# S602X.net
KiCad netlist of a schematic drawn in EAGLE
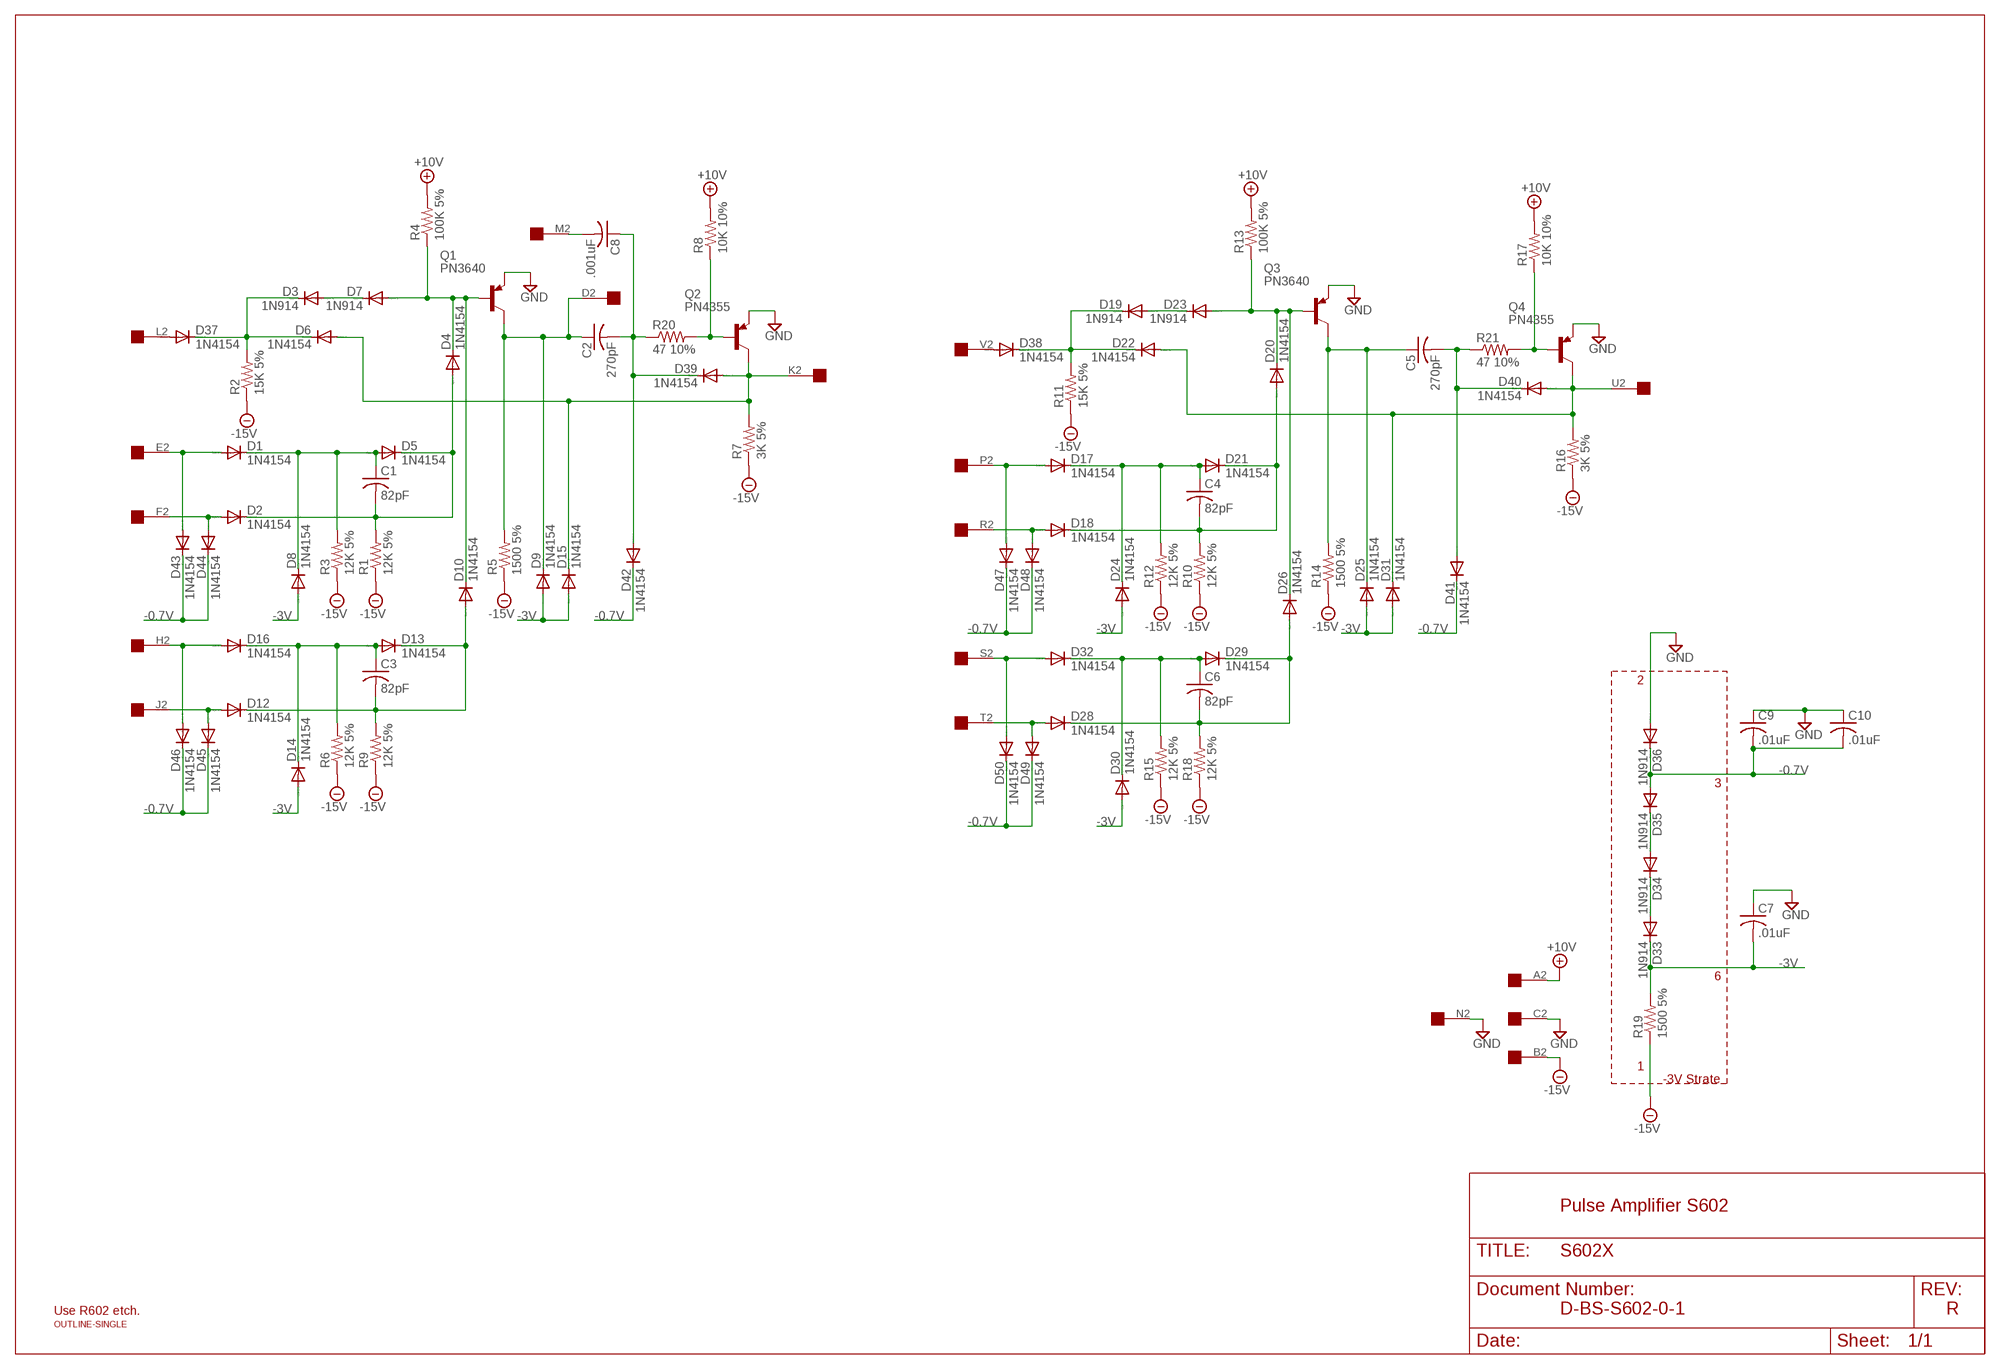
[diagram p0: schematic, sheet 1]

(export (version "E")
  (design (tool "Eeschema 10.0.6"))
  (components
    (comp (ref "C1")
      (value "82pF")
      (footprint "eagle-import:C050-025X075")
      (libsource (lib "eagle-import") (part "C-US050-025X075"))
    )
    (comp (ref "C2")
      (value "270pF")
      (footprint "eagle-import:C050-025X075")
      (libsource (lib "eagle-import") (part "C-US050-025X075"))
    )
    (comp (ref "C3")
      (value "82pF")
      (footprint "eagle-import:C050-025X075")
      (libsource (lib "eagle-import") (part "C-US050-025X075"))
    )
    (comp (ref "C4")
      (value "82pF")
      (footprint "eagle-import:C050-025X075")
      (libsource (lib "eagle-import") (part "C-US050-025X075"))
    )
    (comp (ref "C5")
      (value "270pF")
      (footprint "eagle-import:C050-025X075")
      (libsource (lib "eagle-import") (part "C-US050-025X075"))
    )
    (comp (ref "C6")
      (value "82pF")
      (footprint "eagle-import:C050-025X075")
      (libsource (lib "eagle-import") (part "C-US050-025X075"))
    )
    (comp (ref "C7")
      (value ".01uF")
      (footprint "eagle-import:C075-032X103")
      (libsource (lib "eagle-import") (part "C-US075-032X103"))
    )
    (comp (ref "C8")
      (value ".001uF")
      (footprint "eagle-import:C050-025X075")
      (libsource (lib "eagle-import") (part "C-US050-025X075"))
    )
    (comp (ref "C9")
      (value ".01uF")
      (footprint "eagle-import:C050-025X075")
      (libsource (lib "eagle-import") (part "C-US050-025X075"))
    )
    (comp (ref "C10")
      (value ".01uF")
      (footprint "eagle-import:C050-025X075")
      (libsource (lib "eagle-import") (part "C-US050-025X075"))
    )
    (comp (ref "D1")
      (value "1N4154")
      (footprint "eagle-import:DO35-10")
      (libsource (lib "eagle-import") (part "1N4148DO35-10"))
    )
    (comp (ref "D2")
      (value "1N4154")
      (footprint "eagle-import:DO35-10")
      (libsource (lib "eagle-import") (part "1N4148DO35-10"))
    )
    (comp (ref "D3")
      (value "1N914")
      (footprint "eagle-import:DO35-10")
      (libsource (lib "eagle-import") (part "1N4148DO35-10"))
    )
    (comp (ref "D4")
      (value "1N4154")
      (footprint "eagle-import:DO35-10")
      (libsource (lib "eagle-import") (part "1N4148DO35-10"))
    )
    (comp (ref "D5")
      (value "1N4154")
      (footprint "eagle-import:DO35-10")
      (libsource (lib "eagle-import") (part "1N4148DO35-10"))
    )
    (comp (ref "D6")
      (value "1N4154")
      (footprint "eagle-import:DO35-10")
      (libsource (lib "eagle-import") (part "1N4148DO35-10"))
    )
    (comp (ref "D7")
      (value "1N914")
      (footprint "eagle-import:DO35-10")
      (libsource (lib "eagle-import") (part "1N4148DO35-10"))
    )
    (comp (ref "D8")
      (value "1N4154")
      (footprint "eagle-import:DO35-10")
      (libsource (lib "eagle-import") (part "1N4148DO35-10"))
    )
    (comp (ref "D9")
      (value "1N4154")
      (footprint "eagle-import:DO35-10")
      (libsource (lib "eagle-import") (part "1N4148DO35-10"))
    )
    (comp (ref "D10")
      (value "1N4154")
      (footprint "eagle-import:DO35-10")
      (libsource (lib "eagle-import") (part "1N4148DO35-10"))
    )
    (comp (ref "D12")
      (value "1N4154")
      (footprint "eagle-import:DO35-10")
      (libsource (lib "eagle-import") (part "1N4148DO35-10"))
    )
    (comp (ref "D13")
      (value "1N4154")
      (footprint "eagle-import:DO35-10")
      (libsource (lib "eagle-import") (part "1N4148DO35-10"))
    )
    (comp (ref "D14")
      (value "1N4154")
      (footprint "eagle-import:DO35-10")
      (libsource (lib "eagle-import") (part "1N4148DO35-10"))
    )
    (comp (ref "D15")
      (value "1N4154")
      (footprint "eagle-import:DO35-10")
      (libsource (lib "eagle-import") (part "1N4148DO35-10"))
    )
    (comp (ref "D16")
      (value "1N4154")
      (footprint "eagle-import:DO35-10")
      (libsource (lib "eagle-import") (part "1N4148DO35-10"))
    )
    (comp (ref "D17")
      (value "1N4154")
      (footprint "eagle-import:DO35-10")
      (libsource (lib "eagle-import") (part "1N4148DO35-10"))
    )
    (comp (ref "D18")
      (value "1N4154")
      (footprint "eagle-import:DO35-10")
      (libsource (lib "eagle-import") (part "1N4148DO35-10"))
    )
    (comp (ref "D19")
      (value "1N914")
      (footprint "eagle-import:DO35-10")
      (libsource (lib "eagle-import") (part "1N4148DO35-10"))
    )
    (comp (ref "D20")
      (value "1N4154")
      (footprint "eagle-import:DO35-10")
      (libsource (lib "eagle-import") (part "1N4148DO35-10"))
    )
    (comp (ref "D21")
      (value "1N4154")
      (footprint "eagle-import:DO35-10")
      (libsource (lib "eagle-import") (part "1N4148DO35-10"))
    )
    (comp (ref "D22")
      (value "1N4154")
      (footprint "eagle-import:DO35-10")
      (libsource (lib "eagle-import") (part "1N4148DO35-10"))
    )
    (comp (ref "D23")
      (value "1N914")
      (footprint "eagle-import:DO35-10")
      (libsource (lib "eagle-import") (part "1N4148DO35-10"))
    )
    (comp (ref "D24")
      (value "1N4154")
      (footprint "eagle-import:DO35-10")
      (libsource (lib "eagle-import") (part "1N4148DO35-10"))
    )
    (comp (ref "D25")
      (value "1N4154")
      (footprint "eagle-import:DO35-10")
      (libsource (lib "eagle-import") (part "1N4148DO35-10"))
    )
    (comp (ref "D26")
      (value "1N4154")
      (footprint "eagle-import:DO35-10")
      (libsource (lib "eagle-import") (part "1N4148DO35-10"))
    )
    (comp (ref "D28")
      (value "1N4154")
      (footprint "eagle-import:DO35-10")
      (libsource (lib "eagle-import") (part "1N4148DO35-10"))
    )
    (comp (ref "D29")
      (value "1N4154")
      (footprint "eagle-import:DO35-10")
      (libsource (lib "eagle-import") (part "1N4148DO35-10"))
    )
    (comp (ref "D30")
      (value "1N4154")
      (footprint "eagle-import:DO35-10")
      (libsource (lib "eagle-import") (part "1N4148DO35-10"))
    )
    (comp (ref "D31")
      (value "1N4154")
      (footprint "eagle-import:DO35-10")
      (libsource (lib "eagle-import") (part "1N4148DO35-10"))
    )
    (comp (ref "D32")
      (value "1N4154")
      (footprint "eagle-import:DO35-10")
      (libsource (lib "eagle-import") (part "1N4148DO35-10"))
    )
    (comp (ref "D33")
      (value "1N914")
      (footprint "eagle-import:DO35-10")
      (libsource (lib "eagle-import") (part "1N4148DO35-10"))
    )
    (comp (ref "D34")
      (value "1N914")
      (footprint "eagle-import:DO35-10")
      (libsource (lib "eagle-import") (part "1N4148DO35-10"))
    )
    (comp (ref "D35")
      (value "1N914")
      (footprint "eagle-import:DO35-10")
      (libsource (lib "eagle-import") (part "1N4148DO35-10"))
    )
    (comp (ref "D36")
      (value "1N914")
      (footprint "eagle-import:DO35-10")
      (libsource (lib "eagle-import") (part "1N4148DO35-10"))
    )
    (comp (ref "D37")
      (value "1N4154")
      (footprint "eagle-import:DO35-10")
      (libsource (lib "eagle-import") (part "1N4148DO35-10"))
    )
    (comp (ref "D38")
      (value "1N4154")
      (footprint "eagle-import:DO35-10")
      (libsource (lib "eagle-import") (part "1N4148DO35-10"))
    )
    (comp (ref "D39")
      (value "1N4154")
      (footprint "eagle-import:DO35-10")
      (libsource (lib "eagle-import") (part "1N4148DO35-10"))
    )
    (comp (ref "D40")
      (value "1N4154")
      (footprint "eagle-import:DO35-10")
      (libsource (lib "eagle-import") (part "1N4148DO35-10"))
    )
    (comp (ref "D41")
      (value "1N4154")
      (footprint "eagle-import:DO35-10")
      (libsource (lib "eagle-import") (part "1N4148DO35-10"))
    )
    (comp (ref "D42")
      (value "1N4154")
      (footprint "eagle-import:DO35-10")
      (libsource (lib "eagle-import") (part "1N4148DO35-10"))
    )
    (comp (ref "D43")
      (value "1N4154")
      (footprint "eagle-import:DO35-10")
      (libsource (lib "eagle-import") (part "1N4148DO35-10"))
    )
    (comp (ref "D44")
      (value "1N4154")
      (footprint "eagle-import:DO35-10")
      (libsource (lib "eagle-import") (part "1N4148DO35-10"))
    )
    (comp (ref "D45")
      (value "1N4154")
      (footprint "eagle-import:DO35-10")
      (libsource (lib "eagle-import") (part "1N4148DO35-10"))
    )
    (comp (ref "D46")
      (value "1N4154")
      (footprint "eagle-import:DO35-10")
      (libsource (lib "eagle-import") (part "1N4148DO35-10"))
    )
    (comp (ref "D47")
      (value "1N4154")
      (footprint "eagle-import:DO35-10")
      (libsource (lib "eagle-import") (part "1N4148DO35-10"))
    )
    (comp (ref "D48")
      (value "1N4154")
      (footprint "eagle-import:DO35-10")
      (libsource (lib "eagle-import") (part "1N4148DO35-10"))
    )
    (comp (ref "D49")
      (value "1N4154")
      (footprint "eagle-import:DO35-10")
      (libsource (lib "eagle-import") (part "1N4148DO35-10"))
    )
    (comp (ref "D50")
      (value "1N4154")
      (footprint "eagle-import:DO35-10")
      (libsource (lib "eagle-import") (part "1N4148DO35-10"))
    )
    (comp (ref "Q1")
      (value "PN3640")
      (footprint "eagle-import:TO39")
      (libsource (lib "eagle-import") (part "2N2904"))
    )
    (comp (ref "Q2")
      (value "PN4355")
      (footprint "eagle-import:TO39")
      (libsource (lib "eagle-import") (part "2N2904"))
    )
    (comp (ref "Q3")
      (value "PN3640")
      (footprint "eagle-import:TO39")
      (libsource (lib "eagle-import") (part "2N2904"))
    )
    (comp (ref "Q4")
      (value "PN4355")
      (footprint "eagle-import:TO39")
      (libsource (lib "eagle-import") (part "2N2904"))
    )
    (comp (ref "R1")
      (value "12K 5%")
      (footprint "eagle-import:0207_10")
      (libsource (lib "eagle-import") (part "R-US_0207/10"))
    )
    (comp (ref "R2")
      (value "15K 5%")
      (footprint "eagle-import:0207_10")
      (libsource (lib "eagle-import") (part "R-US_0207/10"))
    )
    (comp (ref "R3")
      (value "12K 5%")
      (footprint "eagle-import:0207_10")
      (libsource (lib "eagle-import") (part "R-US_0207/10"))
    )
    (comp (ref "R4")
      (value "100K 5%")
      (footprint "eagle-import:0207_10")
      (libsource (lib "eagle-import") (part "R-US_0207/10"))
    )
    (comp (ref "R5")
      (value "1500 5%")
      (footprint "eagle-import:0207_10")
      (libsource (lib "eagle-import") (part "R-US_0207/10"))
    )
    (comp (ref "R6")
      (value "12K 5%")
      (footprint "eagle-import:0207_10")
      (libsource (lib "eagle-import") (part "R-US_0207/10"))
    )
    (comp (ref "R7")
      (value "3K 5%")
      (footprint "eagle-import:0207_10")
      (libsource (lib "eagle-import") (part "R-US_0207/10"))
    )
    (comp (ref "R8")
      (value "10K 10%")
      (footprint "eagle-import:0207_10")
      (libsource (lib "eagle-import") (part "R-US_0207/10"))
    )
    (comp (ref "R9")
      (value "12K 5%")
      (footprint "eagle-import:0207_10")
      (libsource (lib "eagle-import") (part "R-US_0207/10"))
    )
    (comp (ref "R10")
      (value "12K 5%")
      (footprint "eagle-import:0207_10")
      (libsource (lib "eagle-import") (part "R-US_0207/10"))
    )
    (comp (ref "R11")
      (value "15K 5%")
      (footprint "eagle-import:0207_10")
      (libsource (lib "eagle-import") (part "R-US_0207/10"))
    )
    (comp (ref "R12")
      (value "12K 5%")
      (footprint "eagle-import:0207_10")
      (libsource (lib "eagle-import") (part "R-US_0207/10"))
    )
    (comp (ref "R13")
      (value "100K 5%")
      (footprint "eagle-import:0207_10")
      (libsource (lib "eagle-import") (part "R-US_0207/10"))
    )
    (comp (ref "R14")
      (value "1500 5%")
      (footprint "eagle-import:0207_10")
      (libsource (lib "eagle-import") (part "R-US_0207/10"))
    )
    (comp (ref "R15")
      (value "12K 5%")
      (footprint "eagle-import:0207_10")
      (libsource (lib "eagle-import") (part "R-US_0207/10"))
    )
    (comp (ref "R16")
      (value "3K 5%")
      (footprint "eagle-import:0207_10")
      (libsource (lib "eagle-import") (part "R-US_0207/10"))
    )
    (comp (ref "R17")
      (value "10K 10%")
      (footprint "eagle-import:0207_10")
      (libsource (lib "eagle-import") (part "R-US_0207/10"))
    )
    (comp (ref "R18")
      (value "12K 5%")
      (footprint "eagle-import:0207_10")
      (libsource (lib "eagle-import") (part "R-US_0207/10"))
    )
    (comp (ref "R19")
      (value "1500 5%")
      (footprint "eagle-import:0207_10")
      (libsource (lib "eagle-import") (part "R-US_0207/10"))
    )
    (comp (ref "R20")
      (value "47 10%")
      (footprint "eagle-import:0207_10")
      (libsource (lib "eagle-import") (part "R-US_0207/10"))
    )
    (comp (ref "R21")
      (value "47 10%")
      (footprint "eagle-import:0207_10")
      (libsource (lib "eagle-import") (part "R-US_0207/10"))
    )
    (comp (ref "U$1")
      (value "OUTLINE-SINGLE")
      (footprint "eagle-import:SINGLE")
      (libsource (lib "eagle-import") (part "OUTLINE-SINGLE"))
    )
    (comp (ref "U$2")
      (value "EDGE-1")
      (footprint "eagle-import:EDGE-CON1")
      (libsource (lib "eagle-import") (part "EDGE-1"))
    )
  )
  (nets
    (net (code "1") (name "+10V") (class "Default")
      (node (ref "R13") (pin "2") (pinfunction "2_2") (pintype "passive"))
      (node (ref "R17") (pin "2") (pinfunction "2_2") (pintype "passive"))
      (node (ref "R4") (pin "2") (pinfunction "2_2") (pintype "passive"))
      (node (ref "R8") (pin "2") (pinfunction "2_2") (pintype "passive"))
      (node (ref "U$2") (pin "A2") (pinfunction "1_A2") (pintype "bidirectional"))
    )
    (net (code "2") (name "-15V") (class "Default")
      (node (ref "R1") (pin "1") (pinfunction "1_1") (pintype "passive"))
      (node (ref "R10") (pin "1") (pinfunction "1_1") (pintype "passive"))
      (node (ref "R11") (pin "1") (pinfunction "1_1") (pintype "passive"))
      (node (ref "R12") (pin "1") (pinfunction "1_1") (pintype "passive"))
      (node (ref "R14") (pin "1") (pinfunction "1_1") (pintype "passive"))
      (node (ref "R15") (pin "1") (pinfunction "1_1") (pintype "passive"))
      (node (ref "R16") (pin "1") (pinfunction "1_1") (pintype "passive"))
      (node (ref "R18") (pin "1") (pinfunction "1_1") (pintype "passive"))
      (node (ref "R19") (pin "1") (pinfunction "1_1") (pintype "passive"))
      (node (ref "R2") (pin "1") (pinfunction "1_1") (pintype "passive"))
      (node (ref "R3") (pin "1") (pinfunction "1_1") (pintype "passive"))
      (node (ref "R5") (pin "1") (pinfunction "1_1") (pintype "passive"))
      (node (ref "R6") (pin "1") (pinfunction "1_1") (pintype "passive"))
      (node (ref "R7") (pin "1") (pinfunction "1_1") (pintype "passive"))
      (node (ref "R9") (pin "1") (pinfunction "1_1") (pintype "passive"))
      (node (ref "U$2") (pin "B2") (pinfunction "1_B2") (pintype "bidirectional"))
    )
    (net (code "3") (name "/-0.7V") (class "Default")
      (node (ref "C10") (pin "2") (pinfunction "2_2") (pintype "passive"))
      (node (ref "C9") (pin "2") (pinfunction "2_2") (pintype "passive"))
      (node (ref "D35") (pin "A") (pinfunction "A_A") (pintype "passive"))
      (node (ref "D36") (pin "C") (pinfunction "C_C") (pintype "passive"))
      (node (ref "D41") (pin "C") (pinfunction "C_C") (pintype "passive"))
      (node (ref "D42") (pin "C") (pinfunction "C_C") (pintype "passive"))
      (node (ref "D43") (pin "C") (pinfunction "C_C") (pintype "passive"))
      (node (ref "D44") (pin "C") (pinfunction "C_C") (pintype "passive"))
      (node (ref "D45") (pin "C") (pinfunction "C_C") (pintype "passive"))
      (node (ref "D46") (pin "C") (pinfunction "C_C") (pintype "passive"))
      (node (ref "D47") (pin "C") (pinfunction "C_C") (pintype "passive"))
      (node (ref "D48") (pin "C") (pinfunction "C_C") (pintype "passive"))
      (node (ref "D49") (pin "C") (pinfunction "C_C") (pintype "passive"))
      (node (ref "D50") (pin "C") (pinfunction "C_C") (pintype "passive"))
    )
    (net (code "4") (name "/-3V") (class "Default")
      (node (ref "C7") (pin "2") (pinfunction "2_2") (pintype "passive"))
      (node (ref "D14") (pin "A") (pinfunction "A_A") (pintype "passive"))
      (node (ref "D15") (pin "A") (pinfunction "A_A") (pintype "passive"))
      (node (ref "D24") (pin "A") (pinfunction "A_A") (pintype "passive"))
      (node (ref "D25") (pin "A") (pinfunction "A_A") (pintype "passive"))
      (node (ref "D30") (pin "A") (pinfunction "A_A") (pintype "passive"))
      (node (ref "D31") (pin "A") (pinfunction "A_A") (pintype "passive"))
      (node (ref "D33") (pin "C") (pinfunction "C_C") (pintype "passive"))
      (node (ref "D8") (pin "A") (pinfunction "A_A") (pintype "passive"))
      (node (ref "D9") (pin "A") (pinfunction "A_A") (pintype "passive"))
      (node (ref "R19") (pin "2") (pinfunction "2_2") (pintype "passive"))
    )
    (net (code "5") (name "GND") (class "Default")
      (node (ref "C10") (pin "1") (pinfunction "1_1") (pintype "passive"))
      (node (ref "C7") (pin "1") (pinfunction "1_1") (pintype "passive"))
      (node (ref "C9") (pin "1") (pinfunction "1_1") (pintype "passive"))
      (node (ref "D36") (pin "A") (pinfunction "A_A") (pintype "passive"))
      (node (ref "Q1") (pin "1") (pinfunction "E_1") (pintype "passive"))
      (node (ref "Q2") (pin "1") (pinfunction "E_1") (pintype "passive"))
      (node (ref "Q3") (pin "1") (pinfunction "E_1") (pintype "passive"))
      (node (ref "Q4") (pin "1") (pinfunction "E_1") (pintype "passive"))
      (node (ref "U$2") (pin "C2") (pinfunction "1_C2") (pintype "bidirectional"))
      (node (ref "U$2") (pin "N2") (pinfunction "1_N2") (pintype "bidirectional"))
    )
    (net (code "6") (name "Net-(C1-Pad1)") (class "Default")
      (node (ref "C1") (pin "1") (pinfunction "1_1") (pintype "passive"))
      (node (ref "D1") (pin "C") (pinfunction "C_C") (pintype "passive"))
      (node (ref "D5") (pin "A") (pinfunction "A_A") (pintype "passive"))
      (node (ref "D8") (pin "C") (pinfunction "C_C") (pintype "passive"))
      (node (ref "R3") (pin "2") (pinfunction "2_2") (pintype "passive"))
    )
    (net (code "7") (name "Net-(C1-Pad2)") (class "Default")
      (node (ref "C1") (pin "2") (pinfunction "2_2") (pintype "passive"))
      (node (ref "D2") (pin "C") (pinfunction "C_C") (pintype "passive"))
      (node (ref "D4") (pin "A") (pinfunction "A_A") (pintype "passive"))
      (node (ref "D5") (pin "C") (pinfunction "C_C") (pintype "passive"))
      (node (ref "R1") (pin "2") (pinfunction "2_2") (pintype "passive"))
    )
    (net (code "8") (name "Net-(C2-Pad2)") (class "Default")
      (node (ref "C2") (pin "2") (pinfunction "2_2") (pintype "passive"))
      (node (ref "C8") (pin "1") (pinfunction "1_1") (pintype "passive"))
      (node (ref "D39") (pin "C") (pinfunction "C_C") (pintype "passive"))
      (node (ref "D42") (pin "A") (pinfunction "A_A") (pintype "passive"))
      (node (ref "R20") (pin "1") (pinfunction "1_1") (pintype "passive"))
    )
    (net (code "9") (name "Net-(C3-Pad1)") (class "Default")
      (node (ref "C3") (pin "1") (pinfunction "1_1") (pintype "passive"))
      (node (ref "D13") (pin "A") (pinfunction "A_A") (pintype "passive"))
      (node (ref "D14") (pin "C") (pinfunction "C_C") (pintype "passive"))
      (node (ref "D16") (pin "C") (pinfunction "C_C") (pintype "passive"))
      (node (ref "R6") (pin "2") (pinfunction "2_2") (pintype "passive"))
    )
    (net (code "10") (name "Net-(C3-Pad2)") (class "Default")
      (node (ref "C3") (pin "2") (pinfunction "2_2") (pintype "passive"))
      (node (ref "D10") (pin "A") (pinfunction "A_A") (pintype "passive"))
      (node (ref "D12") (pin "C") (pinfunction "C_C") (pintype "passive"))
      (node (ref "D13") (pin "C") (pinfunction "C_C") (pintype "passive"))
      (node (ref "R9") (pin "2") (pinfunction "2_2") (pintype "passive"))
    )
    (net (code "11") (name "Net-(C4-Pad1)") (class "Default")
      (node (ref "C4") (pin "1") (pinfunction "1_1") (pintype "passive"))
      (node (ref "D17") (pin "C") (pinfunction "C_C") (pintype "passive"))
      (node (ref "D21") (pin "A") (pinfunction "A_A") (pintype "passive"))
      (node (ref "D24") (pin "C") (pinfunction "C_C") (pintype "passive"))
      (node (ref "R12") (pin "2") (pinfunction "2_2") (pintype "passive"))
    )
    (net (code "12") (name "Net-(C4-Pad2)") (class "Default")
      (node (ref "C4") (pin "2") (pinfunction "2_2") (pintype "passive"))
      (node (ref "D18") (pin "C") (pinfunction "C_C") (pintype "passive"))
      (node (ref "D20") (pin "A") (pinfunction "A_A") (pintype "passive"))
      (node (ref "D21") (pin "C") (pinfunction "C_C") (pintype "passive"))
      (node (ref "R10") (pin "2") (pinfunction "2_2") (pintype "passive"))
    )
    (net (code "13") (name "Net-(C5-Pad2)") (class "Default")
      (node (ref "C5") (pin "2") (pinfunction "2_2") (pintype "passive"))
      (node (ref "D40") (pin "C") (pinfunction "C_C") (pintype "passive"))
      (node (ref "D41") (pin "A") (pinfunction "A_A") (pintype "passive"))
      (node (ref "R21") (pin "1") (pinfunction "1_1") (pintype "passive"))
    )
    (net (code "14") (name "Net-(C6-Pad1)") (class "Default")
      (node (ref "C6") (pin "1") (pinfunction "1_1") (pintype "passive"))
      (node (ref "D29") (pin "A") (pinfunction "A_A") (pintype "passive"))
      (node (ref "D30") (pin "C") (pinfunction "C_C") (pintype "passive"))
      (node (ref "D32") (pin "C") (pinfunction "C_C") (pintype "passive"))
      (node (ref "R15") (pin "2") (pinfunction "2_2") (pintype "passive"))
    )
    (net (code "15") (name "Net-(C6-Pad2)") (class "Default")
      (node (ref "C6") (pin "2") (pinfunction "2_2") (pintype "passive"))
      (node (ref "D26") (pin "A") (pinfunction "A_A") (pintype "passive"))
      (node (ref "D28") (pin "C") (pinfunction "C_C") (pintype "passive"))
      (node (ref "D29") (pin "C") (pinfunction "C_C") (pintype "passive"))
      (node (ref "R18") (pin "2") (pinfunction "2_2") (pintype "passive"))
    )
    (net (code "16") (name "Net-(D3-PadA)") (class "Default")
      (node (ref "D3") (pin "A") (pinfunction "A_A") (pintype "passive"))
      (node (ref "D7") (pin "C") (pinfunction "C_C") (pintype "passive"))
    )
    (net (code "17") (name "Net-(D3-PadC)") (class "Default")
      (node (ref "D3") (pin "C") (pinfunction "C_C") (pintype "passive"))
      (node (ref "D37") (pin "C") (pinfunction "C_C") (pintype "passive"))
      (node (ref "D6") (pin "C") (pinfunction "C_C") (pintype "passive"))
      (node (ref "R2") (pin "2") (pinfunction "2_2") (pintype "passive"))
    )
    (net (code "18") (name "Net-(D19-PadA)") (class "Default")
      (node (ref "D19") (pin "A") (pinfunction "A_A") (pintype "passive"))
      (node (ref "D23") (pin "C") (pinfunction "C_C") (pintype "passive"))
    )
    (net (code "19") (name "Net-(D19-PadC)") (class "Default")
      (node (ref "D19") (pin "C") (pinfunction "C_C") (pintype "passive"))
      (node (ref "D22") (pin "C") (pinfunction "C_C") (pintype "passive"))
      (node (ref "D38") (pin "C") (pinfunction "C_C") (pintype "passive"))
      (node (ref "R11") (pin "2") (pinfunction "2_2") (pintype "passive"))
    )
    (net (code "20") (name "Net-(D33-PadA)") (class "Default")
      (node (ref "D33") (pin "A") (pinfunction "A_A") (pintype "passive"))
      (node (ref "D34") (pin "C") (pinfunction "C_C") (pintype "passive"))
    )
    (net (code "21") (name "Net-(D34-PadA)") (class "Default")
      (node (ref "D34") (pin "A") (pinfunction "A_A") (pintype "passive"))
      (node (ref "D35") (pin "C") (pinfunction "C_C") (pintype "passive"))
    )
    (net (code "22") (name "Net-(Q1-B)") (class "Default")
      (node (ref "D10") (pin "C") (pinfunction "C_C") (pintype "passive"))
      (node (ref "D4") (pin "C") (pinfunction "C_C") (pintype "passive"))
      (node (ref "D7") (pin "A") (pinfunction "A_A") (pintype "passive"))
      (node (ref "Q1") (pin "2") (pinfunction "B_2") (pintype "passive"))
      (node (ref "R4") (pin "1") (pinfunction "1_1") (pintype "passive"))
    )
    (net (code "23") (name "Net-(Q1-C)") (class "Default")
      (node (ref "C2") (pin "1") (pinfunction "1_1") (pintype "passive"))
      (node (ref "D9") (pin "C") (pinfunction "C_C") (pintype "passive"))
      (node (ref "Q1") (pin "3") (pinfunction "C_3") (pintype "passive"))
      (node (ref "R5") (pin "2") (pinfunction "2_2") (pintype "passive"))
      (node (ref "U$2") (pin "D2") (pinfunction "1_D2") (pintype "bidirectional"))
    )
    (net (code "24") (name "Net-(Q2-B)") (class "Default")
      (node (ref "Q2") (pin "2") (pinfunction "B_2") (pintype "passive"))
      (node (ref "R20") (pin "2") (pinfunction "2_2") (pintype "passive"))
      (node (ref "R8") (pin "1") (pinfunction "1_1") (pintype "passive"))
    )
    (net (code "25") (name "Net-(Q2-C)") (class "Default")
      (node (ref "D15") (pin "C") (pinfunction "C_C") (pintype "passive"))
      (node (ref "D39") (pin "A") (pinfunction "A_A") (pintype "passive"))
      (node (ref "D6") (pin "A") (pinfunction "A_A") (pintype "passive"))
      (node (ref "Q2") (pin "3") (pinfunction "C_3") (pintype "passive"))
      (node (ref "R7") (pin "2") (pinfunction "2_2") (pintype "passive"))
      (node (ref "U$2") (pin "K2") (pinfunction "1_K2") (pintype "bidirectional"))
    )
    (net (code "26") (name "Net-(Q3-B)") (class "Default")
      (node (ref "D20") (pin "C") (pinfunction "C_C") (pintype "passive"))
      (node (ref "D23") (pin "A") (pinfunction "A_A") (pintype "passive"))
      (node (ref "D26") (pin "C") (pinfunction "C_C") (pintype "passive"))
      (node (ref "Q3") (pin "2") (pinfunction "B_2") (pintype "passive"))
      (node (ref "R13") (pin "1") (pinfunction "1_1") (pintype "passive"))
    )
    (net (code "27") (name "Net-(Q3-C)") (class "Default")
      (node (ref "C5") (pin "1") (pinfunction "1_1") (pintype "passive"))
      (node (ref "D25") (pin "C") (pinfunction "C_C") (pintype "passive"))
      (node (ref "Q3") (pin "3") (pinfunction "C_3") (pintype "passive"))
      (node (ref "R14") (pin "2") (pinfunction "2_2") (pintype "passive"))
    )
    (net (code "28") (name "Net-(Q4-B)") (class "Default")
      (node (ref "Q4") (pin "2") (pinfunction "B_2") (pintype "passive"))
      (node (ref "R17") (pin "1") (pinfunction "1_1") (pintype "passive"))
      (node (ref "R21") (pin "2") (pinfunction "2_2") (pintype "passive"))
    )
    (net (code "29") (name "Net-(Q4-C)") (class "Default")
      (node (ref "D22") (pin "A") (pinfunction "A_A") (pintype "passive"))
      (node (ref "D31") (pin "C") (pinfunction "C_C") (pintype "passive"))
      (node (ref "D40") (pin "A") (pinfunction "A_A") (pintype "passive"))
      (node (ref "Q4") (pin "3") (pinfunction "C_3") (pintype "passive"))
      (node (ref "R16") (pin "2") (pinfunction "2_2") (pintype "passive"))
      (node (ref "U$2") (pin "U2") (pinfunction "1_U2") (pintype "bidirectional"))
    )
    (net (code "30") (name "Net-(U$2E-1)") (class "Default")
      (node (ref "D1") (pin "A") (pinfunction "A_A") (pintype "passive"))
      (node (ref "D43") (pin "A") (pinfunction "A_A") (pintype "passive"))
      (node (ref "U$2") (pin "E2") (pinfunction "1_E2") (pintype "bidirectional"))
    )
    (net (code "31") (name "Net-(U$2F-1)") (class "Default")
      (node (ref "D2") (pin "A") (pinfunction "A_A") (pintype "passive"))
      (node (ref "D44") (pin "A") (pinfunction "A_A") (pintype "passive"))
      (node (ref "U$2") (pin "F2") (pinfunction "1_F2") (pintype "bidirectional"))
    )
    (net (code "32") (name "Net-(U$2G-1)") (class "Default")
      (node (ref "D16") (pin "A") (pinfunction "A_A") (pintype "passive"))
      (node (ref "D46") (pin "A") (pinfunction "A_A") (pintype "passive"))
      (node (ref "U$2") (pin "H2") (pinfunction "1_H2") (pintype "bidirectional"))
    )
    (net (code "33") (name "Net-(U$2H-1)") (class "Default")
      (node (ref "D12") (pin "A") (pinfunction "A_A") (pintype "passive"))
      (node (ref "D45") (pin "A") (pinfunction "A_A") (pintype "passive"))
      (node (ref "U$2") (pin "J2") (pinfunction "1_J2") (pintype "bidirectional"))
    )
    (net (code "34") (name "Net-(U$2J-1)") (class "Default")
      (node (ref "D37") (pin "A") (pinfunction "A_A") (pintype "passive"))
      (node (ref "U$2") (pin "L2") (pinfunction "1_L2") (pintype "bidirectional"))
    )
    (net (code "35") (name "Net-(U$2K-1)") (class "Default")
      (node (ref "C8") (pin "2") (pinfunction "2_2") (pintype "passive"))
      (node (ref "U$2") (pin "M2") (pinfunction "1_M2") (pintype "bidirectional"))
    )
    (net (code "36") (name "Net-(U$2M-1)") (class "Default")
      (node (ref "D17") (pin "A") (pinfunction "A_A") (pintype "passive"))
      (node (ref "D47") (pin "A") (pinfunction "A_A") (pintype "passive"))
      (node (ref "U$2") (pin "P2") (pinfunction "1_P2") (pintype "bidirectional"))
    )
    (net (code "37") (name "Net-(U$2N-1)") (class "Default")
      (node (ref "D18") (pin "A") (pinfunction "A_A") (pintype "passive"))
      (node (ref "D48") (pin "A") (pinfunction "A_A") (pintype "passive"))
      (node (ref "U$2") (pin "R2") (pinfunction "1_R2") (pintype "bidirectional"))
    )
    (net (code "38") (name "Net-(U$2O-1)") (class "Default")
      (node (ref "D32") (pin "A") (pinfunction "A_A") (pintype "passive"))
      (node (ref "D50") (pin "A") (pinfunction "A_A") (pintype "passive"))
      (node (ref "U$2") (pin "S2") (pinfunction "1_S2") (pintype "bidirectional"))
    )
    (net (code "39") (name "Net-(U$2P-1)") (class "Default")
      (node (ref "D28") (pin "A") (pinfunction "A_A") (pintype "passive"))
      (node (ref "D49") (pin "A") (pinfunction "A_A") (pintype "passive"))
      (node (ref "U$2") (pin "T2") (pinfunction "1_T2") (pintype "bidirectional"))
    )
    (net (code "40") (name "Net-(U$2R-1)") (class "Default")
      (node (ref "D38") (pin "A") (pinfunction "A_A") (pintype "passive"))
      (node (ref "U$2") (pin "V2") (pinfunction "1_V2") (pintype "bidirectional"))
    )
  )
)
